# Cellphone-Detector-2-LM358.net
KiCad netlist of a schematic drawn in EAGLE
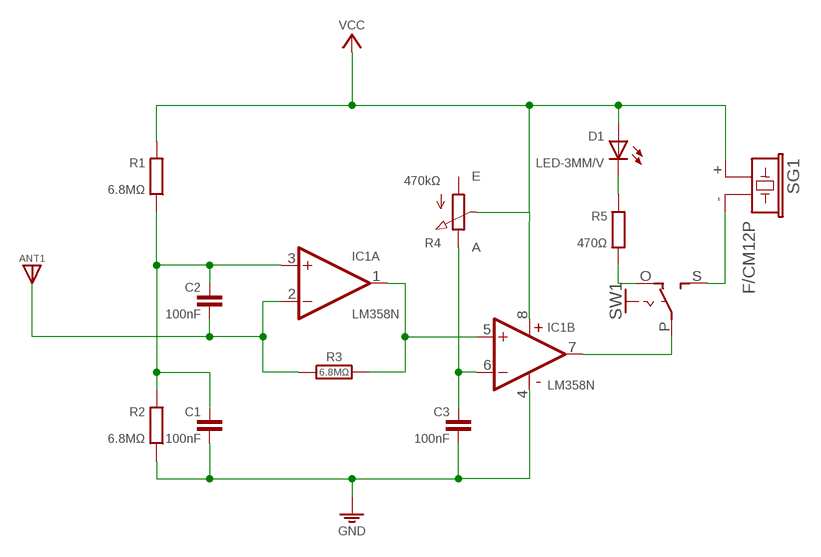
[diagram p0: schematic, sheet 1]

(export (version "E")
  (design (tool "Eeschema 10.0.6"))
  (components
    (comp (ref "ANT1")
      (value "ANT")
      (footprint "eagle-import:SPAD")
      (libsource (lib "eagle-import") (part "ANT"))
    )
    (comp (ref "C1")
      (value "100nF")
      (footprint "eagle-import:C025-024X044")
      (libsource (lib "eagle-import") (part "C025-024X044"))
    )
    (comp (ref "C2")
      (value "100nF")
      (footprint "eagle-import:C025-024X044")
      (libsource (lib "eagle-import") (part "C025-024X044"))
    )
    (comp (ref "C3")
      (value "100nF")
      (footprint "eagle-import:C025-024X044")
      (libsource (lib "eagle-import") (part "C025-024X044"))
    )
    (comp (ref "D1")
      (value "LED-3MM/V")
      (footprint "eagle-import:LED_3MM_V")
      (libsource (lib "eagle-import") (part "LED-3MM/V"))
    )
    (comp (ref "IC1")
      (value "LM358N")
      (footprint "eagle-import:DIL08")
      (libsource (lib "eagle-import") (part "LM358N"))
    )
    (comp (ref "R1")
      (value "6.8MΩ")
      (footprint "eagle-import:0204_7-V")
      (libsource (lib "eagle-import") (part "R0204/7-V"))
    )
    (comp (ref "R2")
      (value "6.8MΩ")
      (footprint "eagle-import:0204_2V")
      (libsource (lib "eagle-import") (part "R0204/2V"))
    )
    (comp (ref "R3")
      (value "6.8MΩ")
      (footprint "eagle-import:0202_2V")
      (libsource (lib "eagle-import") (part "R-H0202/2V"))
    )
    (comp (ref "R4")
      (value "470kΩ")
      (footprint "eagle-import:POT-V")
      (libsource (lib "eagle-import") (part "POT-V"))
    )
    (comp (ref "R5")
      (value "470Ω")
      (footprint "eagle-import:0204_10-V")
      (libsource (lib "eagle-import") (part "R0204/10-V"))
    )
    (comp (ref "S1")
      (value "VCC_GNDPWR-R")
      (footprint "eagle-import:PWR-R")
      (libsource (lib "eagle-import") (part "VCC_GNDPWR-R"))
    )
    (comp (ref "SG1")
      (value "F/CM12P")
      (footprint "eagle-import:F_CM12P")
      (libsource (lib "eagle-import") (part "F/CM12P"))
    )
    (comp (ref "SW1")
      (value "SL-SW-1P-2T-V")
      (footprint "eagle-import:SLSW-1P2T-V")
      (libsource (lib "eagle-import") (part "SL-SW-1P-2T-V"))
    )
  )
  (nets
    (net (code "1") (name "Net-(D1-C)") (class "Default")
      (node (ref "D1") (pin "K") (pinfunction "C_K") (pintype "passive"))
      (node (ref "R5") (pin "1") (pinfunction "2_1") (pintype "passive"))
    )
    (net (code "2") (name "Net-(IC1A-+IN)") (class "Default")
      (node (ref "C1") (pin "1") (pinfunction "1_1") (pintype "passive"))
      (node (ref "C2") (pin "1") (pinfunction "1_1") (pintype "passive"))
      (node (ref "IC1") (pin "3") (pinfunction "+IN_3") (pintype "input"))
      (node (ref "R1") (pin "2") (pinfunction "1_2") (pintype "passive"))
      (node (ref "R2") (pin "1") (pinfunction "2_1") (pintype "passive"))
    )
    (net (code "3") (name "Net-(IC1A--IN)") (class "Default")
      (node (ref "ANT1") (pin "1") (pinfunction "1_1") (pintype "output"))
      (node (ref "C2") (pin "2") (pinfunction "2_2") (pintype "passive"))
      (node (ref "IC1") (pin "2") (pinfunction "-IN_2") (pintype "input"))
      (node (ref "R3") (pin "1") (pinfunction "1_1") (pintype "passive"))
    )
    (net (code "4") (name "Net-(IC1A-OUT)") (class "Default")
      (node (ref "IC1") (pin "1") (pinfunction "OUT_1") (pintype "output"))
      (node (ref "IC1") (pin "5") (pinfunction "+IN_5") (pintype "input"))
      (node (ref "R3") (pin "2") (pinfunction "2_2") (pintype "passive"))
    )
    (net (code "5") (name "Net-(IC1B--IN)") (class "Default")
      (node (ref "C3") (pin "1") (pinfunction "1_1") (pintype "passive"))
      (node (ref "IC1") (pin "6") (pinfunction "-IN_6") (pintype "input"))
      (node (ref "R4") (pin "E") (pinfunction "E_E") (pintype "passive"))
    )
    (net (code "6") (name "Net-(IC1B-OUT)") (class "Default")
      (node (ref "IC1") (pin "7") (pinfunction "OUT_7") (pintype "output"))
      (node (ref "SW1") (pin "P") (pinfunction "P_P") (pintype "passive"))
    )
    (net (code "7") (name "Net-(IC1C-V+)") (class "Default")
      (node (ref "D1") (pin "A") (pinfunction "A_A") (pintype "passive"))
      (node (ref "IC1") (pin "8") (pinfunction "V+_8") (pintype "power_in"))
      (node (ref "R1") (pin "1") (pinfunction "2_1") (pintype "passive"))
      (node (ref "R4") (pin "S") (pinfunction "S_S") (pintype "passive"))
      (node (ref "S1") (pin "2") (pinfunction "VCC_2") (pintype "power_in"))
      (node (ref "SG1") (pin "+") (pinfunction "1_+") (pintype "passive"))
    )
    (net (code "8") (name "Net-(IC1C-V-)") (class "Default")
      (node (ref "C1") (pin "2") (pinfunction "2_2") (pintype "passive"))
      (node (ref "C3") (pin "2") (pinfunction "2_2") (pintype "passive"))
      (node (ref "IC1") (pin "4") (pinfunction "V-_4") (pintype "power_in"))
      (node (ref "R2") (pin "2") (pinfunction "1_2") (pintype "passive"))
      (node (ref "S1") (pin "1") (pinfunction "GND_1") (pintype "power_in"))
    )
    (net (code "9") (name "Net-(R5-1)") (class "Default")
      (node (ref "R5") (pin "2") (pinfunction "1_2") (pintype "passive"))
      (node (ref "SW1") (pin "O") (pinfunction "O_O") (pintype "passive"))
    )
    (net (code "10") (name "Net-(SG1-2)") (class "Default")
      (node (ref "SG1") (pin "-") (pinfunction "2_-") (pintype "passive"))
      (node (ref "SW1") (pin "S") (pinfunction "S_S") (pintype "passive"))
    )
    (net (code "11") (name "unconnected-(R4-PadA)") (class "Default")
      (node (ref "R4") (pin "A") (pinfunction "A_A") (pintype "passive"))
    )
  )
)
